# GateDriver.net
KiCad netlist of a schematic drawn in Altium Designer
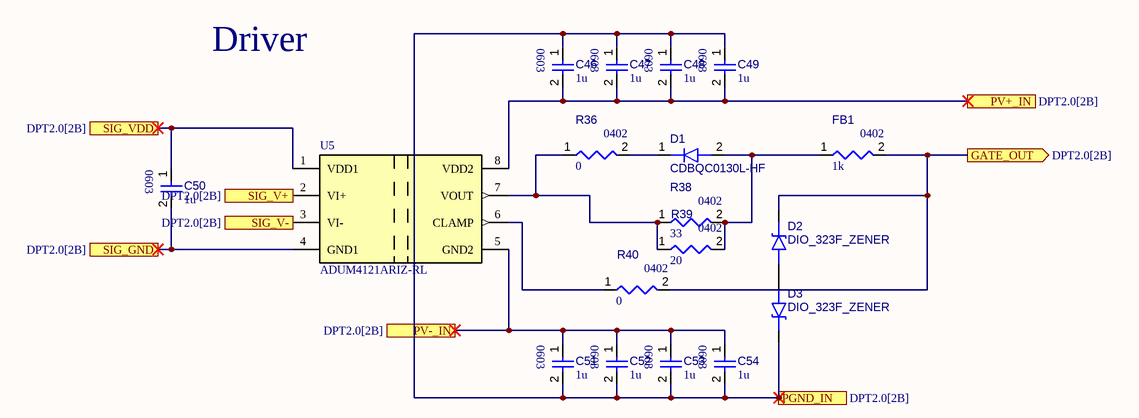
[diagram p0: GateDriver.SchDoc]

(export (version "E")
  (design (tool "Eeschema 10.0.6"))
  (components
    (comp (ref "C46")
      (value "1u")
      (footprint "CAP_0603_HIGH")
      (description "Non polarized SMD capacitor - 0603 (1608 Metric)")
      (fields (field (name "Comment") "CAP-0603"))
      (libsource (lib "2256-GaN Power") (part "CAP-NP-2"))
    )
    (comp (ref "C47")
      (value "1u")
      (footprint "CAP_0603_HIGH")
      (description "Non polarized SMD capacitor - 0603 (1608 Metric)")
      (fields (field (name "Comment") "CAP-0603"))
      (libsource (lib "2256-GaN Power") (part "CAP-NP-2"))
    )
    (comp (ref "C48")
      (value "1u")
      (footprint "CAP_0603_HIGH")
      (description "Non polarized SMD capacitor - 0603 (1608 Metric)")
      (fields (field (name "Comment") "CAP-0603"))
      (libsource (lib "2256-GaN Power") (part "CAP-NP-2"))
    )
    (comp (ref "C49")
      (value "1u")
      (footprint "CAP_0603_HIGH")
      (description "Non polarized SMD capacitor - 0603 (1608 Metric)")
      (fields (field (name "Comment") "CAP-0603"))
      (libsource (lib "2256-GaN Power") (part "CAP-NP-2"))
    )
    (comp (ref "C50")
      (value "1u")
      (footprint "CAP_0603_HIGH")
      (description "Non polarized SMD capacitor - 0603 (1608 Metric)")
      (fields (field (name "Comment") "CAP-0603"))
      (libsource (lib "2256-GaN Power") (part "CAP-NP-2"))
    )
    (comp (ref "C51")
      (value "1u")
      (footprint "CAP_0603_HIGH")
      (description "Non polarized SMD capacitor - 0603 (1608 Metric)")
      (fields (field (name "Comment") "CAP-0603"))
      (libsource (lib "2256-GaN Power") (part "CAP-NP-2"))
    )
    (comp (ref "C52")
      (value "1u")
      (footprint "CAP_0603_HIGH")
      (description "Non polarized SMD capacitor - 0603 (1608 Metric)")
      (fields (field (name "Comment") "CAP-0603"))
      (libsource (lib "2256-GaN Power") (part "CAP-NP-2"))
    )
    (comp (ref "C53")
      (value "1u")
      (footprint "CAP_0603_HIGH")
      (description "Non polarized SMD capacitor - 0603 (1608 Metric)")
      (fields (field (name "Comment") "CAP-0603"))
      (libsource (lib "2256-GaN Power") (part "CAP-NP-2"))
    )
    (comp (ref "C54")
      (value "1u")
      (footprint "CAP_0603_HIGH")
      (description "Non polarized SMD capacitor - 0603 (1608 Metric)")
      (fields (field (name "Comment") "CAP-0603"))
      (libsource (lib "2256-GaN Power") (part "CAP-NP-2"))
    )
    (comp (ref "D1")
      (value "CDBQC0130L-HF")
      (footprint "DIO_SOD-923F")
      (description "Low VF SMD Schottky Barrier Diode")
      (libsource (lib "2256-GaN Power") (part "DIODE-2"))
    )
    (comp (ref "D2")
      (value "DIO_323F_ZENER")
      (footprint "DIO_SOD-323F")
      (description "Generic SOD-323F Zener diode")
      (libsource (lib "2256-GaN Power") (part "DIODE-ZEN-2"))
    )
    (comp (ref "D3")
      (value "DIO_323F_ZENER")
      (footprint "DIO_SOD-323F")
      (description "Generic SOD-323F Zener diode")
      (libsource (lib "2256-GaN Power") (part "DIODE-ZEN-2"))
    )
    (comp (ref "FB1")
      (value "1k")
      (footprint "RES_0402_HIGH")
      (description "SMD Resistor - 0402 (1005 Metric)")
      (fields (field (name "Comment") "RES-0402"))
      (libsource (lib "2256-GaN Power") (part "RES-2"))
    )
    (comp (ref "R36")
      (value "0")
      (footprint "RES_0402_HIGH")
      (description "SMD Resistor - 0402 (1005 Metric)")
      (fields (field (name "Comment") "RES-0402"))
      (libsource (lib "2256-GaN Power") (part "RES-2"))
    )
    (comp (ref "R38")
      (value "33")
      (footprint "RES_0402_HIGH")
      (description "SMD Resistor - 0402 (1005 Metric)")
      (fields (field (name "Comment") "RES-0402"))
      (libsource (lib "2256-GaN Power") (part "RES-2"))
    )
    (comp (ref "R39")
      (value "20")
      (footprint "RES_0402_HIGH")
      (description "SMD Resistor - 0402 (1005 Metric)")
      (fields (field (name "Comment") "RES-0402"))
      (libsource (lib "2256-GaN Power") (part "RES-2"))
    )
    (comp (ref "R40")
      (value "0")
      (footprint "RES_0402_HIGH")
      (description "SMD Resistor - 0402 (1005 Metric)")
      (fields (field (name "Comment") "RES-0402"))
      (libsource (lib "2256-GaN Power") (part "RES-2"))
    )
    (comp (ref "U5")
      (value "ADUM4121ARIZ-RL")
      (footprint "SOIC-8_WIDE")
      (description "DGTL ISO 5KV 1CH GATE DRVR 8SOIC")
      (libsource (lib "2256-GaN Power") (part "ADUM4121"))
    )
  )
  (nets
    (net (code "1") (name "/GATE_OUT") (class "Default")
      (node (ref "D2") (pin "1") (pinfunction "K_1") (pintype "passive"))
      (node (ref "FB1") (pin "2") (pinfunction "2_2") (pintype "passive"))
      (node (ref "R40") (pin "2") (pinfunction "2_2") (pintype "passive"))
    )
    (net (code "2") (name "/PGND_IN") (class "Default")
      (node (ref "C46") (pin "1") (pinfunction "1_1") (pintype "passive"))
      (node (ref "C47") (pin "1") (pinfunction "1_1") (pintype "passive"))
      (node (ref "C48") (pin "1") (pinfunction "1_1") (pintype "passive"))
      (node (ref "C49") (pin "1") (pinfunction "1_1") (pintype "passive"))
      (node (ref "C51") (pin "2") (pinfunction "2_2") (pintype "passive"))
      (node (ref "C52") (pin "2") (pinfunction "2_2") (pintype "passive"))
      (node (ref "C53") (pin "2") (pinfunction "2_2") (pintype "passive"))
      (node (ref "C54") (pin "2") (pinfunction "2_2") (pintype "passive"))
      (node (ref "D3") (pin "1") (pinfunction "K_1") (pintype "passive"))
    )
    (net (code "3") (name "/PV+_IN") (class "Default")
      (node (ref "C46") (pin "2") (pinfunction "2_2") (pintype "passive"))
      (node (ref "C47") (pin "2") (pinfunction "2_2") (pintype "passive"))
      (node (ref "C48") (pin "2") (pinfunction "2_2") (pintype "passive"))
      (node (ref "C49") (pin "2") (pinfunction "2_2") (pintype "passive"))
      (node (ref "U5") (pin "8") (pinfunction "VDD2_8") (pintype "power_in"))
    )
    (net (code "4") (name "/PV-_IN") (class "Default")
      (node (ref "C51") (pin "1") (pinfunction "1_1") (pintype "passive"))
      (node (ref "C52") (pin "1") (pinfunction "1_1") (pintype "passive"))
      (node (ref "C53") (pin "1") (pinfunction "1_1") (pintype "passive"))
      (node (ref "C54") (pin "1") (pinfunction "1_1") (pintype "passive"))
      (node (ref "U5") (pin "5") (pinfunction "GND2_5") (pintype "power_in"))
    )
    (net (code "5") (name "/SIG_GND") (class "Default")
      (node (ref "C50") (pin "2") (pinfunction "2_2") (pintype "passive"))
      (node (ref "U5") (pin "4") (pinfunction "GND1_4") (pintype "power_in"))
    )
    (net (code "6") (name "/SIG_V+") (class "Default")
      (node (ref "U5") (pin "2") (pinfunction "VI+_2") (pintype "passive"))
    )
    (net (code "7") (name "/SIG_V-") (class "Default")
      (node (ref "U5") (pin "3") (pinfunction "VI-_3") (pintype "passive"))
    )
    (net (code "8") (name "/SIG_VDD") (class "Default")
      (node (ref "C50") (pin "1") (pinfunction "1_1") (pintype "passive"))
      (node (ref "U5") (pin "1") (pinfunction "VDD1_1") (pintype "power_in"))
    )
    (net (code "9") (name "Net-(D1-A)") (class "Default")
      (node (ref "D1") (pin "2") (pinfunction "A_2") (pintype "passive"))
      (node (ref "FB1") (pin "1") (pinfunction "1_1") (pintype "passive"))
      (node (ref "R38") (pin "2") (pinfunction "2_2") (pintype "passive"))
      (node (ref "R39") (pin "2") (pinfunction "2_2") (pintype "passive"))
    )
    (net (code "10") (name "Net-(D1-K)") (class "Default")
      (node (ref "D1") (pin "1") (pinfunction "K_1") (pintype "passive"))
      (node (ref "R36") (pin "2") (pinfunction "2_2") (pintype "passive"))
    )
    (net (code "11") (name "Net-(D2-A)") (class "Default")
      (node (ref "D2") (pin "2") (pinfunction "A_2") (pintype "passive"))
      (node (ref "D3") (pin "2") (pinfunction "A_2") (pintype "passive"))
    )
    (net (code "12") (name "Net-(U5-CLAMP)") (class "Default")
      (node (ref "R40") (pin "1") (pinfunction "1_1") (pintype "passive"))
      (node (ref "U5") (pin "6") (pinfunction "CLAMP_6") (pintype "output"))
    )
    (net (code "13") (name "Net-(U5-VOUT)") (class "Default")
      (node (ref "R36") (pin "1") (pinfunction "1_1") (pintype "passive"))
      (node (ref "R38") (pin "1") (pinfunction "1_1") (pintype "passive"))
      (node (ref "R39") (pin "1") (pinfunction "1_1") (pintype "passive"))
      (node (ref "U5") (pin "7") (pinfunction "VOUT_7") (pintype "output"))
    )
  )
)
